# DemoSensor.net
KiCad netlist of a schematic drawn in EAGLE
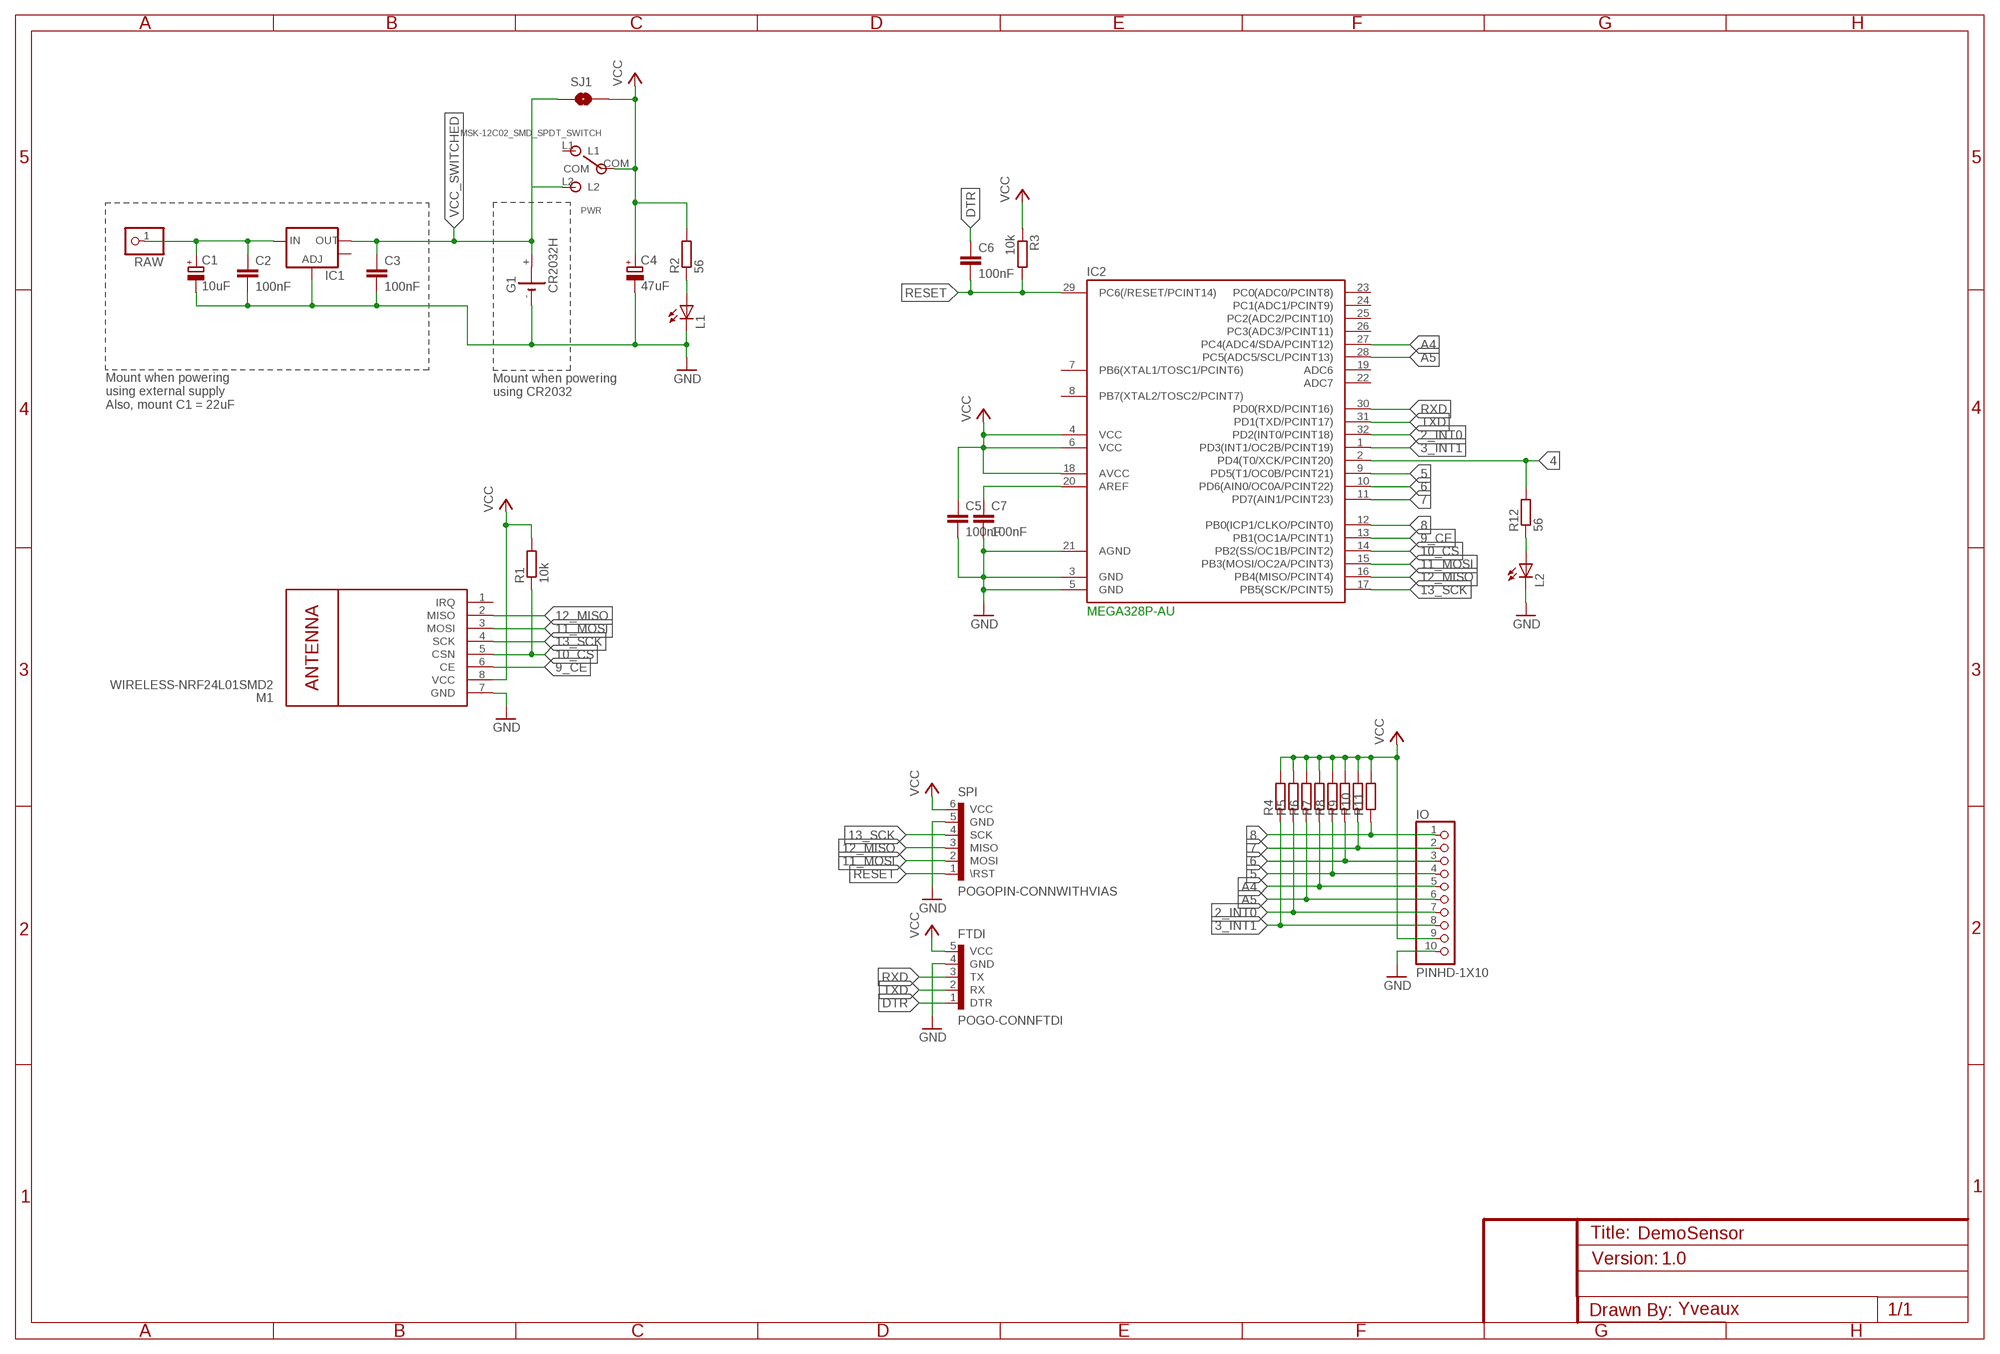
[diagram p0: schematic, sheet 1]

(export (version "E")
  (design (tool "Eeschema 10.0.6"))
  (components
    (comp (ref "C1")
      (value "10uF")
      (footprint "eagle-import:SMC_A")
      (libsource (lib "eagle-import") (part "CPOL-EUSMCA"))
    )
    (comp (ref "C2")
      (value "100nF")
      (footprint "eagle-import:C0603")
      (libsource (lib "eagle-import") (part "C-EUC0603"))
    )
    (comp (ref "C3")
      (value "100nF")
      (footprint "eagle-import:C0603")
      (libsource (lib "eagle-import") (part "C-EUC0603"))
    )
    (comp (ref "C4")
      (value "47uF")
      (footprint "eagle-import:SMC_A")
      (libsource (lib "eagle-import") (part "CPOL-EUSMCA"))
    )
    (comp (ref "C5")
      (value "100nF")
      (footprint "eagle-import:C0603")
      (libsource (lib "eagle-import") (part "C-EUC0603"))
    )
    (comp (ref "C6")
      (value "100nF")
      (footprint "eagle-import:C0603")
      (libsource (lib "eagle-import") (part "C-EUC0603"))
    )
    (comp (ref "C7")
      (value "100nF")
      (footprint "eagle-import:C0603")
      (libsource (lib "eagle-import") (part "C-EUC0603"))
    )
    (comp (ref "FTDI")
      (value "POGO-CONNFTDI")
      (footprint "eagle-import:POGO5-VIAS")
      (libsource (lib "eagle-import") (part "POGO-CONNFTDI"))
    )
    (comp (ref "G1")
      (value "CR2032H")
      (footprint "eagle-import:CR2032H")
      (libsource (lib "eagle-import") (part "CR2032H"))
    )
    (comp (ref "IC1")
      (value "V_REG_LM1117SOT223")
      (footprint "eagle-import:SOT223")
      (libsource (lib "eagle-import") (part "V_REG_LM1117SOT223"))
    )
    (comp (ref "IC2")
      (value "MEGA328P-AU")
      (footprint "eagle-import:TQFP32-08")
      (libsource (lib "eagle-import") (part "MEGA48/88/168-AU"))
    )
    (comp (ref "IO")
      (value "PINHD-1X10")
      (footprint "eagle-import:1X10-BIG")
      (libsource (lib "eagle-import") (part "PINHD-1X10"))
    )
    (comp (ref "L1")
      (value "LEDCHIPLED_0603")
      (footprint "eagle-import:CHIPLED_0603")
      (libsource (lib "eagle-import") (part "LEDCHIPLED_0603"))
    )
    (comp (ref "L2")
      (value "LEDCHIPLED_0603")
      (footprint "eagle-import:CHIPLED_0603")
      (libsource (lib "eagle-import") (part "LEDCHIPLED_0603"))
    )
    (comp (ref "M1")
      (value "WIRELESS-NRF24L01SMD2")
      (footprint "eagle-import:WIRELESS-NRF24L01-SMD-2")
      (libsource (lib "eagle-import") (part "WIRELESS-NRF24L01SMD2"))
    )
    (comp (ref "PWR")
      (value "MSK-12C02_SMD_SPDT_SWITCH")
      (footprint "eagle-import:MSK-12C02")
      (libsource (lib "eagle-import") (part "MSK-12C02_SMD_SPDT_SWITCH"))
    )
    (comp (ref "R1")
      (value "10k")
      (footprint "eagle-import:R0603")
      (libsource (lib "eagle-import") (part "R-EU_R0603"))
    )
    (comp (ref "R2")
      (value "56")
      (footprint "eagle-import:R0603")
      (libsource (lib "eagle-import") (part "R-EU_R0603"))
    )
    (comp (ref "R3")
      (value "10k")
      (footprint "eagle-import:R0603")
      (libsource (lib "eagle-import") (part "R-EU_R0603"))
    )
    (comp (ref "R4")
      (value "R-EU_R0603")
      (footprint "eagle-import:R0603")
      (libsource (lib "eagle-import") (part "R-EU_R0603"))
    )
    (comp (ref "R5")
      (value "R-EU_R0603")
      (footprint "eagle-import:R0603")
      (libsource (lib "eagle-import") (part "R-EU_R0603"))
    )
    (comp (ref "R6")
      (value "R-EU_R0603")
      (footprint "eagle-import:R0603")
      (libsource (lib "eagle-import") (part "R-EU_R0603"))
    )
    (comp (ref "R7")
      (value "R-EU_R0603")
      (footprint "eagle-import:R0603")
      (libsource (lib "eagle-import") (part "R-EU_R0603"))
    )
    (comp (ref "R8")
      (value "R-EU_R0603")
      (footprint "eagle-import:R0603")
      (libsource (lib "eagle-import") (part "R-EU_R0603"))
    )
    (comp (ref "R9")
      (value "R-EU_R0603")
      (footprint "eagle-import:R0603")
      (libsource (lib "eagle-import") (part "R-EU_R0603"))
    )
    (comp (ref "R10")
      (value "R-EU_R0603")
      (footprint "eagle-import:R0603")
      (libsource (lib "eagle-import") (part "R-EU_R0603"))
    )
    (comp (ref "R11")
      (value "R-EU_R0603")
      (footprint "eagle-import:R0603")
      (libsource (lib "eagle-import") (part "R-EU_R0603"))
    )
    (comp (ref "R12")
      (value "56")
      (footprint "eagle-import:R0603")
      (libsource (lib "eagle-import") (part "R-EU_R0603"))
    )
    (comp (ref "RAW")
      (value "PINHD-1X1")
      (footprint "eagle-import:1X01")
      (libsource (lib "eagle-import") (part "PINHD-1X1"))
    )
    (comp (ref "SJ1")
      (value "SOLDERJUMPERNO")
      (footprint "eagle-import:SJ_2S-NO")
      (libsource (lib "eagle-import") (part "SOLDERJUMPERNO"))
    )
    (comp (ref "SPI")
      (value "POGOPIN-CONNWITHVIAS")
      (footprint "eagle-import:POGOPROG-CONN-0H")
      (libsource (lib "eagle-import") (part "POGOPIN-CONNWITHVIAS"))
    )
  )
  (nets
    (net (code "1") (name "2_INT0") (class "Default")
      (node (ref "IC2") (pin "32") (pinfunction "PD2(INT0/PCINT18)_32") (pintype "bidirectional"))
      (node (ref "IO") (pin "7") (pinfunction "7_7") (pintype "passive"))
      (node (ref "R5") (pin "1") (pinfunction "1_1") (pintype "passive"))
    )
    (net (code "2") (name "3_INT1") (class "Default")
      (node (ref "IC2") (pin "1") (pinfunction "PD3(INT1/OC2B/PCINT19)_1") (pintype "bidirectional"))
      (node (ref "IO") (pin "8") (pinfunction "8_8") (pintype "passive"))
      (node (ref "R4") (pin "1") (pinfunction "1_1") (pintype "passive"))
    )
    (net (code "3") (name "4") (class "Default")
      (node (ref "IC2") (pin "2") (pinfunction "PD4(T0/XCK/PCINT20)_2") (pintype "bidirectional"))
      (node (ref "R12") (pin "2") (pinfunction "2_2") (pintype "passive"))
    )
    (net (code "4") (name "5") (class "Default")
      (node (ref "IC2") (pin "9") (pinfunction "PD5(T1/OC0B/PCINT21)_9") (pintype "bidirectional"))
      (node (ref "IO") (pin "4") (pinfunction "4_4") (pintype "passive"))
      (node (ref "R8") (pin "1") (pinfunction "1_1") (pintype "passive"))
    )
    (net (code "5") (name "6") (class "Default")
      (node (ref "IC2") (pin "10") (pinfunction "PD6(AIN0/OC0A/PCINT22)_10") (pintype "bidirectional"))
      (node (ref "IO") (pin "3") (pinfunction "3_3") (pintype "passive"))
      (node (ref "R9") (pin "1") (pinfunction "1_1") (pintype "passive"))
    )
    (net (code "6") (name "7") (class "Default")
      (node (ref "IC2") (pin "11") (pinfunction "PD7(AIN1/PCINT23)_11") (pintype "bidirectional"))
      (node (ref "IO") (pin "2") (pinfunction "2_2") (pintype "passive"))
      (node (ref "R10") (pin "1") (pinfunction "1_1") (pintype "passive"))
    )
    (net (code "7") (name "8") (class "Default")
      (node (ref "IC2") (pin "12") (pinfunction "PB0(ICP1/CLKO/PCINT0)_12") (pintype "bidirectional"))
      (node (ref "IO") (pin "1") (pinfunction "1_1") (pintype "passive"))
      (node (ref "R11") (pin "1") (pinfunction "1_1") (pintype "passive"))
    )
    (net (code "8") (name "9_CE") (class "Default")
      (node (ref "IC2") (pin "13") (pinfunction "PB1(OC1A/PCINT1)_13") (pintype "bidirectional"))
      (node (ref "M1") (pin "6") (pinfunction "CE_6") (pintype "bidirectional"))
    )
    (net (code "9") (name "10_CS") (class "Default")
      (node (ref "IC2") (pin "14") (pinfunction "PB2(SS/OC1B/PCINT2)_14") (pintype "bidirectional"))
      (node (ref "M1") (pin "5") (pinfunction "CSN_5") (pintype "bidirectional"))
      (node (ref "R1") (pin "1") (pinfunction "1_1") (pintype "passive"))
    )
    (net (code "10") (name "11_MOSI") (class "Default")
      (node (ref "IC2") (pin "15") (pinfunction "PB3(MOSI/OC2A/PCINT3)_15") (pintype "bidirectional"))
      (node (ref "M1") (pin "3") (pinfunction "MOSI_3") (pintype "bidirectional"))
      (node (ref "SPI") (pin "2") (pinfunction "MOSI_2") (pintype "bidirectional"))
    )
    (net (code "11") (name "12_MISO") (class "Default")
      (node (ref "IC2") (pin "16") (pinfunction "PB4(MISO/PCINT4)_16") (pintype "bidirectional"))
      (node (ref "M1") (pin "2") (pinfunction "MISO_2") (pintype "bidirectional"))
      (node (ref "SPI") (pin "3") (pinfunction "MISO_3") (pintype "bidirectional"))
    )
    (net (code "12") (name "13_SCK") (class "Default")
      (node (ref "IC2") (pin "17") (pinfunction "PB5(SCK/PCINT5)_17") (pintype "bidirectional"))
      (node (ref "M1") (pin "4") (pinfunction "SCK_4") (pintype "bidirectional"))
      (node (ref "SPI") (pin "4") (pinfunction "SCK_4") (pintype "bidirectional"))
    )
    (net (code "13") (name "A4") (class "Default")
      (node (ref "IC2") (pin "27") (pinfunction "PC4(ADC4/SDA/PCINT12)_27") (pintype "bidirectional"))
      (node (ref "IO") (pin "5") (pinfunction "5_5") (pintype "passive"))
      (node (ref "R7") (pin "1") (pinfunction "1_1") (pintype "passive"))
    )
    (net (code "14") (name "A5") (class "Default")
      (node (ref "IC2") (pin "28") (pinfunction "PC5(ADC5/SCL/PCINT13)_28") (pintype "bidirectional"))
      (node (ref "IO") (pin "6") (pinfunction "6_6") (pintype "passive"))
      (node (ref "R6") (pin "1") (pinfunction "1_1") (pintype "passive"))
    )
    (net (code "15") (name "DTR") (class "Default")
      (node (ref "C6") (pin "1") (pinfunction "1_1") (pintype "passive"))
      (node (ref "FTDI") (pin "1") (pinfunction "DTR_1") (pintype "bidirectional"))
    )
    (net (code "16") (name "GND") (class "Default")
      (node (ref "C1") (pin "-") (pinfunction "-_-") (pintype "passive"))
      (node (ref "C2") (pin "2") (pinfunction "2_2") (pintype "passive"))
      (node (ref "C3") (pin "2") (pinfunction "2_2") (pintype "passive"))
      (node (ref "C4") (pin "-") (pinfunction "-_-") (pintype "passive"))
      (node (ref "C5") (pin "2") (pinfunction "2_2") (pintype "passive"))
      (node (ref "C7") (pin "2") (pinfunction "2_2") (pintype "passive"))
      (node (ref "FTDI") (pin "4") (pinfunction "GND_4") (pintype "bidirectional"))
      (node (ref "G1") (pin "-") (pinfunction "-_-") (pintype "passive"))
      (node (ref "IC1") (pin "1") (pinfunction "ADJ_1") (pintype "input"))
      (node (ref "IC2") (pin "21") (pinfunction "AGND_21") (pintype "power_in"))
      (node (ref "IC2") (pin "3") (pinfunction "GND_3") (pintype "power_in"))
      (node (ref "IC2") (pin "5") (pinfunction "GND_5") (pintype "power_in"))
      (node (ref "IO") (pin "10") (pinfunction "10_10") (pintype "passive"))
      (node (ref "L1") (pin "C") (pinfunction "C_C") (pintype "passive"))
      (node (ref "L2") (pin "C") (pinfunction "C_C") (pintype "passive"))
      (node (ref "M1") (pin "7") (pinfunction "GND_7") (pintype "power_in"))
      (node (ref "SPI") (pin "5") (pinfunction "GND_5") (pintype "bidirectional"))
    )
    (net (code "17") (name "Net-(IC1-IN)") (class "Default")
      (node (ref "C1") (pin "+") (pinfunction "+_+") (pintype "passive"))
      (node (ref "C2") (pin "1") (pinfunction "1_1") (pintype "passive"))
      (node (ref "IC1") (pin "3") (pinfunction "IN_3") (pintype "input"))
      (node (ref "RAW") (pin "1") (pinfunction "1_1") (pintype "passive"))
    )
    (net (code "18") (name "Net-(IC2-AREF)") (class "Default")
      (node (ref "C7") (pin "1") (pinfunction "1_1") (pintype "passive"))
      (node (ref "IC2") (pin "20") (pinfunction "AREF_20") (pintype "passive"))
    )
    (net (code "19") (name "Net-(L1-PadA)") (class "Default")
      (node (ref "L1") (pin "A") (pinfunction "A_A") (pintype "passive"))
      (node (ref "R2") (pin "1") (pinfunction "1_1") (pintype "passive"))
    )
    (net (code "20") (name "Net-(L2-PadA)") (class "Default")
      (node (ref "L2") (pin "A") (pinfunction "A_A") (pintype "passive"))
      (node (ref "R12") (pin "1") (pinfunction "1_1") (pintype "passive"))
    )
    (net (code "21") (name "RESET") (class "Default")
      (node (ref "C6") (pin "2") (pinfunction "2_2") (pintype "passive"))
      (node (ref "IC2") (pin "29") (pinfunction "PC6(/RESET/PCINT14)_29") (pintype "bidirectional"))
      (node (ref "R3") (pin "2") (pinfunction "2_2") (pintype "passive"))
      (node (ref "SPI") (pin "1") (pinfunction "\\RST_1") (pintype "bidirectional"))
    )
    (net (code "22") (name "RXD") (class "Default")
      (node (ref "FTDI") (pin "3") (pinfunction "TX_3") (pintype "bidirectional"))
      (node (ref "IC2") (pin "30") (pinfunction "PD0(RXD/PCINT16)_30") (pintype "bidirectional"))
    )
    (net (code "23") (name "TXD") (class "Default")
      (node (ref "FTDI") (pin "2") (pinfunction "RX_2") (pintype "bidirectional"))
      (node (ref "IC2") (pin "31") (pinfunction "PD1(TXD/PCINT17)_31") (pintype "bidirectional"))
    )
    (net (code "24") (name "VCC") (class "Default")
      (node (ref "C4") (pin "+") (pinfunction "+_+") (pintype "passive"))
      (node (ref "C5") (pin "1") (pinfunction "1_1") (pintype "passive"))
      (node (ref "FTDI") (pin "5") (pinfunction "VCC_5") (pintype "bidirectional"))
      (node (ref "IC2") (pin "18") (pinfunction "AVCC_18") (pintype "passive"))
      (node (ref "IC2") (pin "4") (pinfunction "VCC_4") (pintype "power_in"))
      (node (ref "IC2") (pin "6") (pinfunction "VCC_6") (pintype "power_in"))
      (node (ref "IO") (pin "9") (pinfunction "9_9") (pintype "passive"))
      (node (ref "M1") (pin "8") (pinfunction "VCC_8") (pintype "power_in"))
      (node (ref "PWR") (pin "COM") (pinfunction "COM_COM") (pintype "bidirectional"))
      (node (ref "R1") (pin "2") (pinfunction "2_2") (pintype "passive"))
      (node (ref "R10") (pin "2") (pinfunction "2_2") (pintype "passive"))
      (node (ref "R11") (pin "2") (pinfunction "2_2") (pintype "passive"))
      (node (ref "R2") (pin "2") (pinfunction "2_2") (pintype "passive"))
      (node (ref "R3") (pin "1") (pinfunction "1_1") (pintype "passive"))
      (node (ref "R4") (pin "2") (pinfunction "2_2") (pintype "passive"))
      (node (ref "R5") (pin "2") (pinfunction "2_2") (pintype "passive"))
      (node (ref "R6") (pin "2") (pinfunction "2_2") (pintype "passive"))
      (node (ref "R7") (pin "2") (pinfunction "2_2") (pintype "passive"))
      (node (ref "R8") (pin "2") (pinfunction "2_2") (pintype "passive"))
      (node (ref "R9") (pin "2") (pinfunction "2_2") (pintype "passive"))
      (node (ref "SJ1") (pin "2") (pinfunction "2_2") (pintype "passive"))
      (node (ref "SPI") (pin "6") (pinfunction "VCC_6") (pintype "bidirectional"))
    )
    (net (code "25") (name "VCC_SWITCHED") (class "Default")
      (node (ref "C3") (pin "1") (pinfunction "1_1") (pintype "passive"))
      (node (ref "G1") (pin "+") (pinfunction "+_+") (pintype "passive"))
      (node (ref "IC1") (pin "2") (pinfunction "OUT_2") (pintype "output"))
      (node (ref "PWR") (pin "L2") (pinfunction "L2_L2") (pintype "bidirectional"))
      (node (ref "SJ1") (pin "1") (pinfunction "1_1") (pintype "passive"))
    )
    (net (code "26") (name "unconnected-(IC1-OUT-Pad4)") (class "Default")
      (node (ref "IC1") (pin "4") (pinfunction "OUT_4") (pintype "output"))
    )
    (net (code "27") (name "unconnected-(IC2-ADC6-Pad19)") (class "Default")
      (node (ref "IC2") (pin "19") (pinfunction "ADC6_19") (pintype "passive"))
    )
    (net (code "28") (name "unconnected-(IC2-ADC7-Pad22)") (class "Default")
      (node (ref "IC2") (pin "22") (pinfunction "ADC7_22") (pintype "passive"))
    )
    (net (code "29") (name "unconnected-(IC2-PB6(XTAL1{slash}TOSC1{slash}PCINT6)-Pad7)") (class "Default")
      (node (ref "IC2") (pin "7") (pinfunction "PB6(XTAL1/TOSC1/PCINT6)_7") (pintype "bidirectional"))
    )
    (net (code "30") (name "unconnected-(IC2-PB7(XTAL2{slash}TOSC2{slash}PCINT7)-Pad8)") (class "Default")
      (node (ref "IC2") (pin "8") (pinfunction "PB7(XTAL2/TOSC2/PCINT7)_8") (pintype "bidirectional"))
    )
    (net (code "31") (name "unconnected-(IC2-PC0(ADC0{slash}PCINT8)-Pad23)") (class "Default")
      (node (ref "IC2") (pin "23") (pinfunction "PC0(ADC0/PCINT8)_23") (pintype "bidirectional"))
    )
    (net (code "32") (name "unconnected-(IC2-PC1(ADC1{slash}PCINT9)-Pad24)") (class "Default")
      (node (ref "IC2") (pin "24") (pinfunction "PC1(ADC1/PCINT9)_24") (pintype "bidirectional"))
    )
    (net (code "33") (name "unconnected-(IC2-PC2(ADC2{slash}PCINT10)-Pad25)") (class "Default")
      (node (ref "IC2") (pin "25") (pinfunction "PC2(ADC2/PCINT10)_25") (pintype "bidirectional"))
    )
    (net (code "34") (name "unconnected-(IC2-PC3(ADC3{slash}PCINT11)-Pad26)") (class "Default")
      (node (ref "IC2") (pin "26") (pinfunction "PC3(ADC3/PCINT11)_26") (pintype "bidirectional"))
    )
    (net (code "35") (name "unconnected-(M1-IRQ-Pad1)") (class "Default")
      (node (ref "M1") (pin "1") (pinfunction "IRQ_1") (pintype "bidirectional"))
    )
    (net (code "36") (name "unconnected-(PWR-PadL1)") (class "Default")
      (node (ref "PWR") (pin "L1") (pinfunction "L1_L1") (pintype "bidirectional"))
    )
  )
)
